# Pi-Display-2.net
KiCad netlist of a schematic drawn in EAGLE
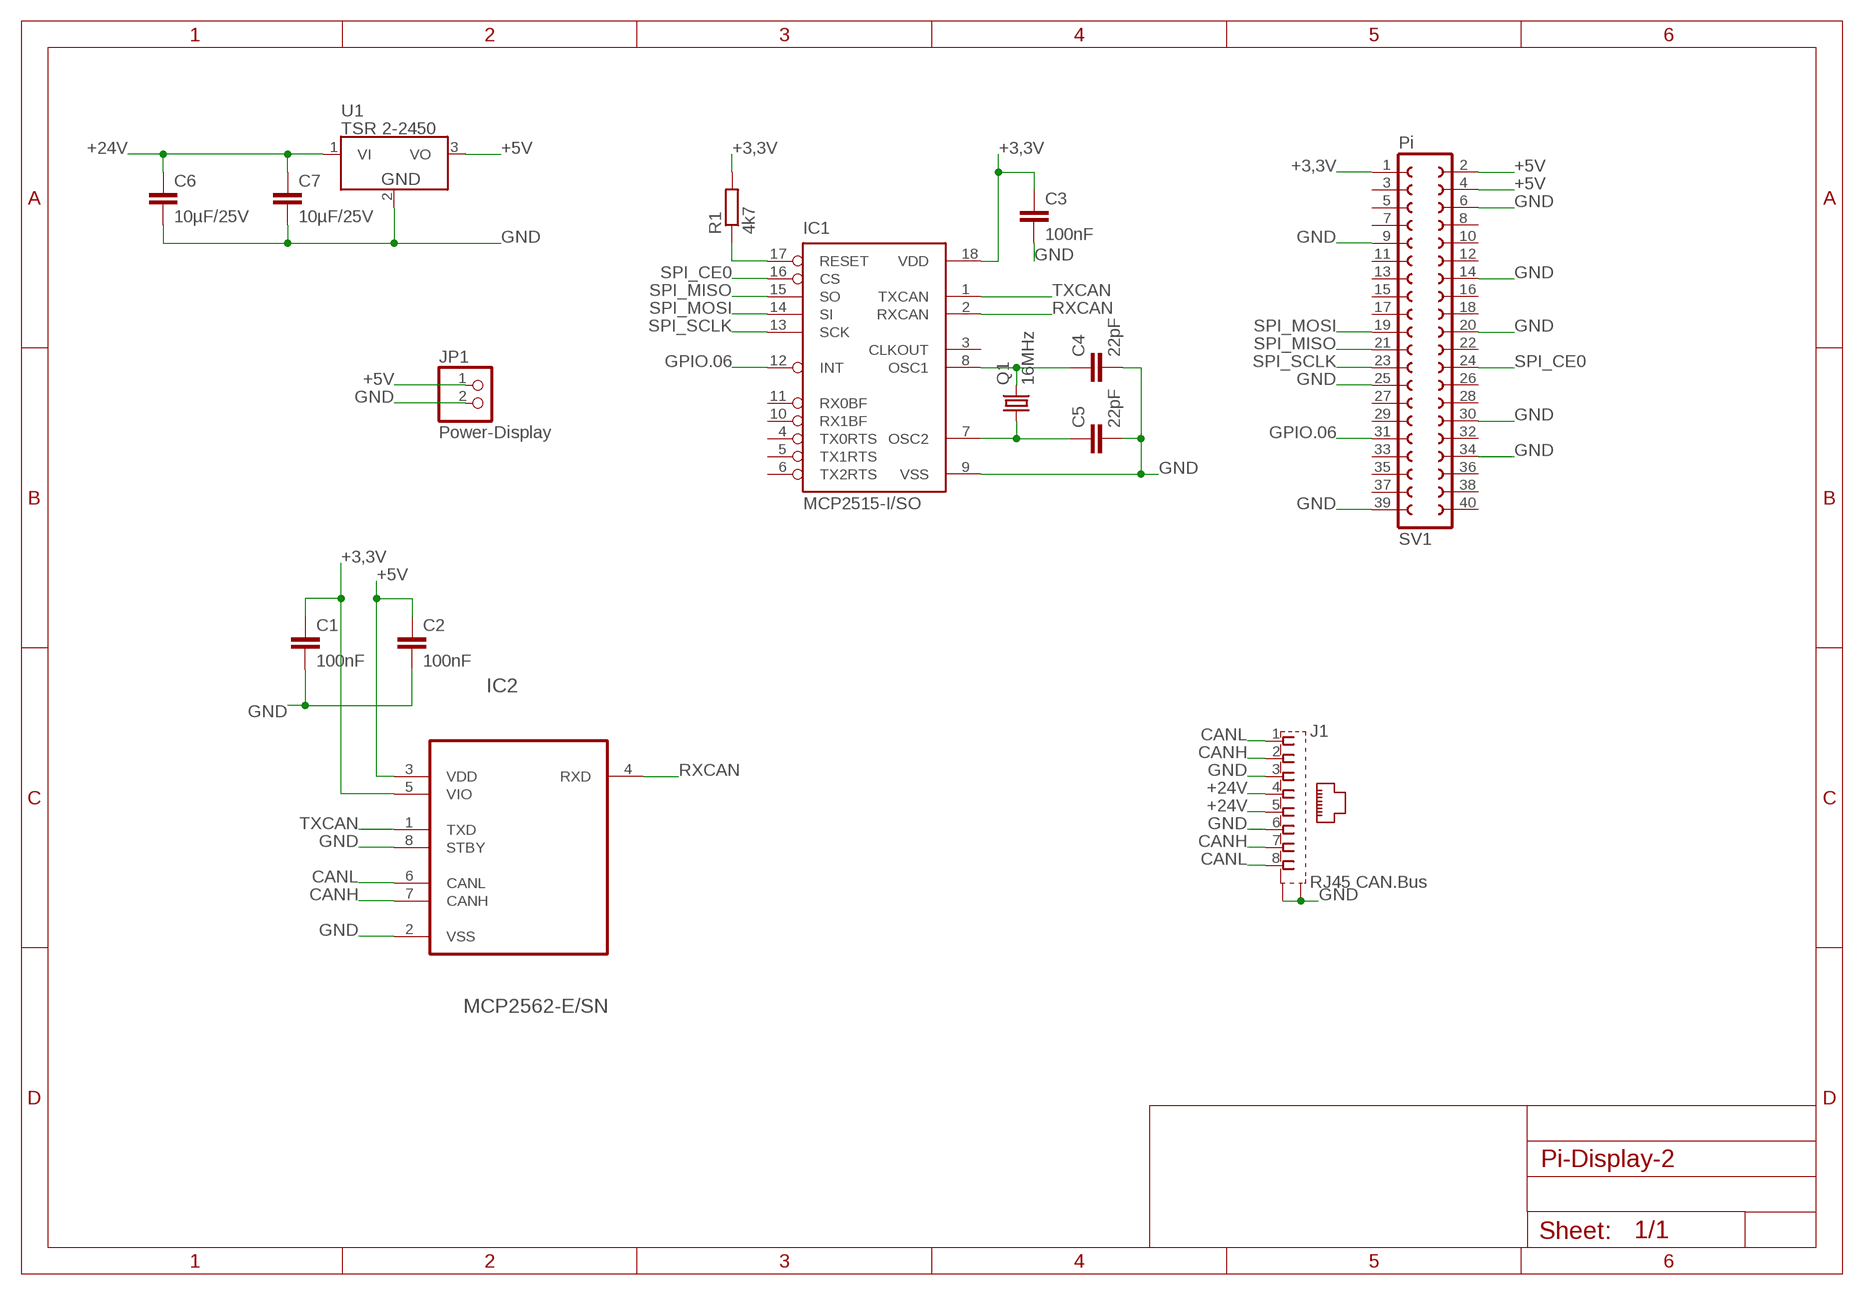
[diagram p0: schematic, sheet 1]

(export (version "E")
  (design (tool "Eeschema 10.0.6"))
  (components
    (comp (ref "C1")
      (value "100nF")
      (footprint "eagle-import:C1206")
      (libsource (lib "eagle-import") (part "C-EUC1206"))
    )
    (comp (ref "C2")
      (value "100nF")
      (footprint "eagle-import:C1206")
      (libsource (lib "eagle-import") (part "C-EUC1206"))
    )
    (comp (ref "C3")
      (value "100nF")
      (footprint "eagle-import:C1206")
      (libsource (lib "eagle-import") (part "C-EUC1206"))
    )
    (comp (ref "C4")
      (value "22pF")
      (footprint "eagle-import:C1206")
      (libsource (lib "eagle-import") (part "C-EUC1206"))
    )
    (comp (ref "C5")
      (value "22pF")
      (footprint "eagle-import:C1206")
      (libsource (lib "eagle-import") (part "C-EUC1206"))
    )
    (comp (ref "C6")
      (value "10µF/25V")
      (footprint "eagle-import:C1206")
      (libsource (lib "eagle-import") (part "C-EUC1206"))
    )
    (comp (ref "C7")
      (value "10µF/25V")
      (footprint "eagle-import:C1206")
      (libsource (lib "eagle-import") (part "C-EUC1206"))
    )
    (comp (ref "IC1")
      (value "MCP2515-I/SO")
      (footprint "eagle-import:SO18L")
      (libsource (lib "eagle-import") (part "MCP2515-I/SO"))
    )
    (comp (ref "IC2")
      (value "MCP2562-E/SN")
      (footprint "eagle-import:SO08")
      (libsource (lib "eagle-import") (part "MCP2562-E/SN"))
    )
    (comp (ref "J1")
      (value "RJ45 CAN.Bus")
      (footprint "eagle-import:MEBP_8-8G")
      (libsource (lib "eagle-import") (part "555141-1"))
    )
    (comp (ref "JP1")
      (value "Power-Display")
      (footprint "eagle-import:1X02_90")
      (libsource (lib "eagle-import") (part "PINHD-1X2/90"))
    )
    (comp (ref "Q1")
      (value "16MHz")
      (footprint "eagle-import:HC49UP")
      (libsource (lib "eagle-import") (part "CRYSTALHC49UP"))
    )
    (comp (ref "R1")
      (value "4k7")
      (footprint "eagle-import:R1206")
      (libsource (lib "eagle-import") (part "R-EU_R1206"))
    )
    (comp (ref "SV1")
      (value "Pi")
      (footprint "eagle-import:FE20-2")
      (libsource (lib "eagle-import") (part "FE20-2"))
    )
    (comp (ref "U1")
      (value "TSR 2-2450")
      (footprint "eagle-import:TSR2")
      (libsource (lib "eagle-import") (part "TSR2-2450"))
    )
  )
  (nets
    (net (code "1") (name "/+3,3V") (class "Default")
      (node (ref "C1") (pin "1") (pinfunction "1_1") (pintype "passive"))
      (node (ref "C3") (pin "1") (pinfunction "1_1") (pintype "passive"))
      (node (ref "IC1") (pin "18") (pinfunction "VDD_18") (pintype "power_in"))
      (node (ref "IC2") (pin "5") (pinfunction "VIO_5") (pintype "power_in"))
      (node (ref "R1") (pin "2") (pinfunction "2_2") (pintype "passive"))
      (node (ref "SV1") (pin "1") (pinfunction "1_1") (pintype "passive"))
    )
    (net (code "2") (name "/+5V") (class "Default")
      (node (ref "C2") (pin "1") (pinfunction "1_1") (pintype "passive"))
      (node (ref "IC2") (pin "3") (pinfunction "VDD_3") (pintype "power_in"))
      (node (ref "JP1") (pin "1") (pinfunction "1_1") (pintype "passive"))
      (node (ref "SV1") (pin "2") (pinfunction "2_2") (pintype "passive"))
      (node (ref "SV1") (pin "4") (pinfunction "4_4") (pintype "passive"))
      (node (ref "U1") (pin "3") (pinfunction "VO_3") (pintype "power_in"))
    )
    (net (code "3") (name "/+24V") (class "Default")
      (node (ref "C6") (pin "1") (pinfunction "1_1") (pintype "passive"))
      (node (ref "C7") (pin "1") (pinfunction "1_1") (pintype "passive"))
      (node (ref "J1") (pin "4") (pinfunction "4_4") (pintype "passive"))
      (node (ref "J1") (pin "5") (pinfunction "5_5") (pintype "passive"))
      (node (ref "U1") (pin "1") (pinfunction "VI_1") (pintype "power_in"))
    )
    (net (code "4") (name "/CANH") (class "Default")
      (node (ref "IC2") (pin "7") (pinfunction "CANH_7") (pintype "bidirectional"))
      (node (ref "J1") (pin "2") (pinfunction "2_2") (pintype "passive"))
      (node (ref "J1") (pin "7") (pinfunction "7_7") (pintype "passive"))
    )
    (net (code "5") (name "/CANL") (class "Default")
      (node (ref "IC2") (pin "6") (pinfunction "CANL_6") (pintype "bidirectional"))
      (node (ref "J1") (pin "1") (pinfunction "1_1") (pintype "passive"))
      (node (ref "J1") (pin "8") (pinfunction "8_8") (pintype "passive"))
    )
    (net (code "6") (name "/GND") (class "Default")
      (node (ref "C1") (pin "2") (pinfunction "2_2") (pintype "passive"))
      (node (ref "C2") (pin "2") (pinfunction "2_2") (pintype "passive"))
      (node (ref "C3") (pin "2") (pinfunction "2_2") (pintype "passive"))
      (node (ref "C4") (pin "2") (pinfunction "2_2") (pintype "passive"))
      (node (ref "C5") (pin "2") (pinfunction "2_2") (pintype "passive"))
      (node (ref "C6") (pin "2") (pinfunction "2_2") (pintype "passive"))
      (node (ref "C7") (pin "2") (pinfunction "2_2") (pintype "passive"))
      (node (ref "IC1") (pin "9") (pinfunction "VSS_9") (pintype "power_in"))
      (node (ref "IC2") (pin "2") (pinfunction "VSS_2") (pintype "power_in"))
      (node (ref "IC2") (pin "8") (pinfunction "STBY_8") (pintype "input"))
      (node (ref "J1") (pin "3") (pinfunction "3_3") (pintype "passive"))
      (node (ref "J1") (pin "6") (pinfunction "6_6") (pintype "passive"))
      (node (ref "J1") (pin "G1") (pinfunction "S1_G1") (pintype "passive"))
      (node (ref "J1") (pin "G2") (pinfunction "S2_G2") (pintype "passive"))
      (node (ref "JP1") (pin "2") (pinfunction "2_2") (pintype "passive"))
      (node (ref "SV1") (pin "14") (pinfunction "14_14") (pintype "passive"))
      (node (ref "SV1") (pin "20") (pinfunction "20_20") (pintype "passive"))
      (node (ref "SV1") (pin "25") (pinfunction "25_25") (pintype "passive"))
      (node (ref "SV1") (pin "30") (pinfunction "30_30") (pintype "passive"))
      (node (ref "SV1") (pin "34") (pinfunction "34_34") (pintype "passive"))
      (node (ref "SV1") (pin "39") (pinfunction "39_39") (pintype "passive"))
      (node (ref "SV1") (pin "6") (pinfunction "6_6") (pintype "passive"))
      (node (ref "SV1") (pin "9") (pinfunction "9_9") (pintype "passive"))
      (node (ref "U1") (pin "2") (pinfunction "GND_2") (pintype "power_in"))
    )
    (net (code "7") (name "/GPIO.06") (class "Default")
      (node (ref "IC1") (pin "12") (pinfunction "INT_12") (pintype "output"))
      (node (ref "SV1") (pin "31") (pinfunction "31_31") (pintype "passive"))
    )
    (net (code "8") (name "/RXCAN") (class "Default")
      (node (ref "IC1") (pin "2") (pinfunction "RXCAN_2") (pintype "input"))
      (node (ref "IC2") (pin "4") (pinfunction "RXD_4") (pintype "output"))
    )
    (net (code "9") (name "/SPI_CE0") (class "Default")
      (node (ref "IC1") (pin "16") (pinfunction "CS_16") (pintype "input"))
      (node (ref "SV1") (pin "24") (pinfunction "24_24") (pintype "passive"))
    )
    (net (code "10") (name "/SPI_MISO") (class "Default")
      (node (ref "IC1") (pin "15") (pinfunction "SO_15") (pintype "output"))
      (node (ref "SV1") (pin "21") (pinfunction "21_21") (pintype "passive"))
    )
    (net (code "11") (name "/SPI_MOSI") (class "Default")
      (node (ref "IC1") (pin "14") (pinfunction "SI_14") (pintype "input"))
      (node (ref "SV1") (pin "19") (pinfunction "19_19") (pintype "passive"))
    )
    (net (code "12") (name "/SPI_SCLK") (class "Default")
      (node (ref "IC1") (pin "13") (pinfunction "SCK_13") (pintype "input"))
      (node (ref "SV1") (pin "23") (pinfunction "23_23") (pintype "passive"))
    )
    (net (code "13") (name "/TXCAN") (class "Default")
      (node (ref "IC1") (pin "1") (pinfunction "TXCAN_1") (pintype "output"))
      (node (ref "IC2") (pin "1") (pinfunction "TXD_1") (pintype "input"))
    )
    (net (code "14") (name "Net-(IC1-OSC1)") (class "Default")
      (node (ref "C4") (pin "1") (pinfunction "1_1") (pintype "passive"))
      (node (ref "IC1") (pin "8") (pinfunction "OSC1_8") (pintype "input"))
      (node (ref "Q1") (pin "2") (pinfunction "2_2") (pintype "passive"))
    )
    (net (code "15") (name "Net-(IC1-OSC2)") (class "Default")
      (node (ref "C5") (pin "1") (pinfunction "1_1") (pintype "passive"))
      (node (ref "IC1") (pin "7") (pinfunction "OSC2_7") (pintype "output"))
      (node (ref "Q1") (pin "1") (pinfunction "1_1") (pintype "passive"))
    )
    (net (code "16") (name "Net-(IC1-RESET)") (class "Default")
      (node (ref "IC1") (pin "17") (pinfunction "RESET_17") (pintype "input"))
      (node (ref "R1") (pin "1") (pinfunction "1_1") (pintype "passive"))
    )
    (net (code "17") (name "unconnected-(IC1-CLKOUT-Pad3)") (class "Default")
      (node (ref "IC1") (pin "3") (pinfunction "CLKOUT_3") (pintype "output"))
    )
    (net (code "18") (name "unconnected-(IC1-RX0BF-Pad11)") (class "Default")
      (node (ref "IC1") (pin "11") (pinfunction "RX0BF_11") (pintype "output"))
    )
    (net (code "19") (name "unconnected-(IC1-RX1BF-Pad10)") (class "Default")
      (node (ref "IC1") (pin "10") (pinfunction "RX1BF_10") (pintype "output"))
    )
    (net (code "20") (name "unconnected-(IC1-TX0RTS-Pad4)") (class "Default")
      (node (ref "IC1") (pin "4") (pinfunction "TX0RTS_4") (pintype "input"))
    )
    (net (code "21") (name "unconnected-(IC1-TX1RTS-Pad5)") (class "Default")
      (node (ref "IC1") (pin "5") (pinfunction "TX1RTS_5") (pintype "input"))
    )
    (net (code "22") (name "unconnected-(IC1-TX2RTS-Pad6)") (class "Default")
      (node (ref "IC1") (pin "6") (pinfunction "TX2RTS_6") (pintype "input"))
    )
    (net (code "23") (name "unconnected-(SV1-Pad3)") (class "Default")
      (node (ref "SV1") (pin "3") (pinfunction "3_3") (pintype "passive"))
    )
    (net (code "24") (name "unconnected-(SV1-Pad5)") (class "Default")
      (node (ref "SV1") (pin "5") (pinfunction "5_5") (pintype "passive"))
    )
    (net (code "25") (name "unconnected-(SV1-Pad7)") (class "Default")
      (node (ref "SV1") (pin "7") (pinfunction "7_7") (pintype "passive"))
    )
    (net (code "26") (name "unconnected-(SV1-Pad8)") (class "Default")
      (node (ref "SV1") (pin "8") (pinfunction "8_8") (pintype "passive"))
    )
    (net (code "27") (name "unconnected-(SV1-Pad10)") (class "Default")
      (node (ref "SV1") (pin "10") (pinfunction "10_10") (pintype "passive"))
    )
    (net (code "28") (name "unconnected-(SV1-Pad11)") (class "Default")
      (node (ref "SV1") (pin "11") (pinfunction "11_11") (pintype "passive"))
    )
    (net (code "29") (name "unconnected-(SV1-Pad12)") (class "Default")
      (node (ref "SV1") (pin "12") (pinfunction "12_12") (pintype "passive"))
    )
    (net (code "30") (name "unconnected-(SV1-Pad13)") (class "Default")
      (node (ref "SV1") (pin "13") (pinfunction "13_13") (pintype "passive"))
    )
    (net (code "31") (name "unconnected-(SV1-Pad15)") (class "Default")
      (node (ref "SV1") (pin "15") (pinfunction "15_15") (pintype "passive"))
    )
    (net (code "32") (name "unconnected-(SV1-Pad16)") (class "Default")
      (node (ref "SV1") (pin "16") (pinfunction "16_16") (pintype "passive"))
    )
    (net (code "33") (name "unconnected-(SV1-Pad17)") (class "Default")
      (node (ref "SV1") (pin "17") (pinfunction "17_17") (pintype "passive"))
    )
    (net (code "34") (name "unconnected-(SV1-Pad18)") (class "Default")
      (node (ref "SV1") (pin "18") (pinfunction "18_18") (pintype "passive"))
    )
    (net (code "35") (name "unconnected-(SV1-Pad22)") (class "Default")
      (node (ref "SV1") (pin "22") (pinfunction "22_22") (pintype "passive"))
    )
    (net (code "36") (name "unconnected-(SV1-Pad26)") (class "Default")
      (node (ref "SV1") (pin "26") (pinfunction "26_26") (pintype "passive"))
    )
    (net (code "37") (name "unconnected-(SV1-Pad27)") (class "Default")
      (node (ref "SV1") (pin "27") (pinfunction "27_27") (pintype "passive"))
    )
    (net (code "38") (name "unconnected-(SV1-Pad28)") (class "Default")
      (node (ref "SV1") (pin "28") (pinfunction "28_28") (pintype "passive"))
    )
    (net (code "39") (name "unconnected-(SV1-Pad29)") (class "Default")
      (node (ref "SV1") (pin "29") (pinfunction "29_29") (pintype "passive"))
    )
    (net (code "40") (name "unconnected-(SV1-Pad32)") (class "Default")
      (node (ref "SV1") (pin "32") (pinfunction "32_32") (pintype "passive"))
    )
    (net (code "41") (name "unconnected-(SV1-Pad33)") (class "Default")
      (node (ref "SV1") (pin "33") (pinfunction "33_33") (pintype "passive"))
    )
    (net (code "42") (name "unconnected-(SV1-Pad35)") (class "Default")
      (node (ref "SV1") (pin "35") (pinfunction "35_35") (pintype "passive"))
    )
    (net (code "43") (name "unconnected-(SV1-Pad36)") (class "Default")
      (node (ref "SV1") (pin "36") (pinfunction "36_36") (pintype "passive"))
    )
    (net (code "44") (name "unconnected-(SV1-Pad37)") (class "Default")
      (node (ref "SV1") (pin "37") (pinfunction "37_37") (pintype "passive"))
    )
    (net (code "45") (name "unconnected-(SV1-Pad38)") (class "Default")
      (node (ref "SV1") (pin "38") (pinfunction "38_38") (pintype "passive"))
    )
    (net (code "46") (name "unconnected-(SV1-Pad40)") (class "Default")
      (node (ref "SV1") (pin "40") (pinfunction "40_40") (pintype "passive"))
    )
  )
)
